# openhum3.net
KiCad netlist of a schematic drawn in EAGLE
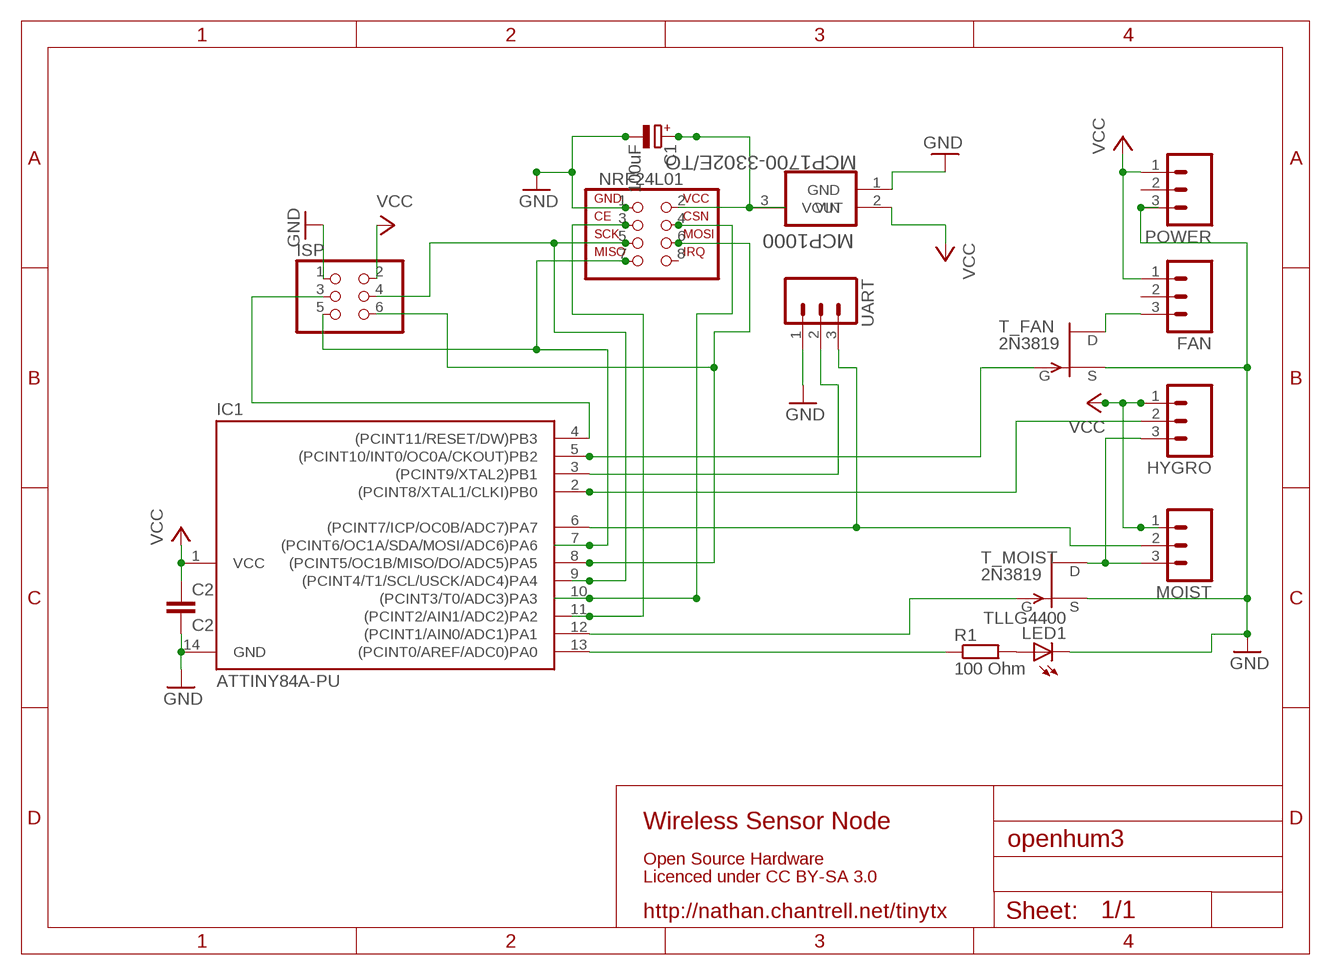
[diagram p0: schematic, sheet 1]

(export (version "E")
  (design (tool "Eeschema 10.0.6"))
  (components
    (comp (ref "C1")
      (value "100uF")
      (footprint "eagle-import:E2,5-6")
      (libsource (lib "eagle-import") (part "CPOL-EUE2.5-6"))
    )
    (comp (ref "C2")
      (value "C2")
      (footprint "eagle-import:C025-025X050")
      (libsource (lib "eagle-import") (part "C-EU025-025X050"))
    )
    (comp (ref "FAN")
      (value "M03JST-PTH")
      (footprint "eagle-import:JST-3-PTH")
      (libsource (lib "eagle-import") (part "M03JST-PTH"))
    )
    (comp (ref "HYGRO")
      (value "M03JST-PTH")
      (footprint "eagle-import:JST-3-PTH")
      (libsource (lib "eagle-import") (part "M03JST-PTH"))
    )
    (comp (ref "IC1")
      (value "ATTINY84A-PU")
      (footprint "eagle-import:DIL14")
      (libsource (lib "eagle-import") (part "TINY24/44/84-PU"))
    )
    (comp (ref "ISP")
      (value "PINHD-2X3")
      (footprint "eagle-import:2X03")
      (libsource (lib "eagle-import") (part "PINHD-2X3"))
    )
    (comp (ref "LED1")
      (value "TLLG4400")
      (footprint "eagle-import:LED3MM")
      (fields (field (name "MF") "VISHAY SEMICONDUCTOR"))
      (libsource (lib "eagle-import") (part "TLLG4400"))
    )
    (comp (ref "MCP1000")
      (value "MCP1700-3302E/TO")
      (footprint "eagle-import:TO127P254X495-3")
      (libsource (lib "eagle-import") (part "MCP1700-3302E/TO"))
    )
    (comp (ref "MOIST")
      (value "M03JST-PTH")
      (footprint "eagle-import:JST-3-PTH")
      (libsource (lib "eagle-import") (part "M03JST-PTH"))
    )
    (comp (ref "NRF24L01")
      (value "NRF24L01+")
      (footprint "eagle-import:NRF24L01+")
      (libsource (lib "eagle-import") (part "NRF24L01+"))
    )
    (comp (ref "POWER")
      (value "M03JST-PTH")
      (footprint "eagle-import:JST-3-PTH")
      (libsource (lib "eagle-import") (part "M03JST-PTH"))
    )
    (comp (ref "R1")
      (value "100 Ohm")
      (footprint "eagle-import:0204_5")
      (libsource (lib "eagle-import") (part "R-EU_0204/5"))
    )
    (comp (ref "T_FAN")
      (value "2N3819")
      (footprint "eagle-import:TO92")
      (libsource (lib "eagle-import") (part "2N3819"))
    )
    (comp (ref "T_MOIST")
      (value "2N3819")
      (footprint "eagle-import:TO92")
      (libsource (lib "eagle-import") (part "2N3819"))
    )
    (comp (ref "UART")
      (value "M03JST-PTH")
      (footprint "eagle-import:JST-3-PTH")
      (libsource (lib "eagle-import") (part "M03JST-PTH"))
    )
  )
  (nets
    (net (code "1") (name "GND") (class "Default")
      (node (ref "C1") (pin "-") (pinfunction "-_-") (pintype "passive"))
      (node (ref "C2") (pin "2") (pinfunction "2_2") (pintype "passive"))
      (node (ref "IC1") (pin "14") (pinfunction "GND_14") (pintype "power_in"))
      (node (ref "ISP") (pin "1") (pinfunction "1_1") (pintype "passive"))
      (node (ref "LED1") (pin "K") (pinfunction "C_K") (pintype "passive"))
      (node (ref "MCP1000") (pin "1") (pinfunction "GND_1") (pintype "passive"))
      (node (ref "NRF24L01") (pin "1") (pinfunction "1_1") (pintype "passive"))
      (node (ref "POWER") (pin "3") (pinfunction "3_3") (pintype "passive"))
      (node (ref "T_FAN") (pin "3") (pinfunction "S_3") (pintype "passive"))
      (node (ref "T_MOIST") (pin "3") (pinfunction "S_3") (pintype "passive"))
      (node (ref "UART") (pin "1") (pinfunction "1_1") (pintype "passive"))
    )
    (net (code "2") (name "Net-(IC1-(PCINT0{slash}AREF{slash}ADC0)PA0)") (class "Default")
      (node (ref "IC1") (pin "13") (pinfunction "(PCINT0/AREF/ADC0)PA0_13") (pintype "bidirectional"))
      (node (ref "R1") (pin "1") (pinfunction "1_1") (pintype "passive"))
    )
    (net (code "3") (name "Net-(IC1-(PCINT1{slash}AIN0{slash}ADC1)PA1)") (class "Default")
      (node (ref "IC1") (pin "12") (pinfunction "(PCINT1/AIN0/ADC1)PA1_12") (pintype "bidirectional"))
      (node (ref "T_MOIST") (pin "2") (pinfunction "G_2") (pintype "passive"))
    )
    (net (code "4") (name "Net-(IC1-(PCINT2{slash}AIN1{slash}ADC2)PA2)") (class "Default")
      (node (ref "IC1") (pin "11") (pinfunction "(PCINT2/AIN1/ADC2)PA2_11") (pintype "bidirectional"))
      (node (ref "NRF24L01") (pin "3") (pinfunction "3_3") (pintype "passive"))
    )
    (net (code "5") (name "Net-(IC1-(PCINT3{slash}T0{slash}ADC3)PA3)") (class "Default")
      (node (ref "IC1") (pin "10") (pinfunction "(PCINT3/T0/ADC3)PA3_10") (pintype "bidirectional"))
      (node (ref "NRF24L01") (pin "4") (pinfunction "4_4") (pintype "passive"))
    )
    (net (code "6") (name "Net-(IC1-(PCINT4{slash}T1{slash}SCL{slash}USCK{slash}ADC4)PA4)") (class "Default")
      (node (ref "IC1") (pin "9") (pinfunction "(PCINT4/T1/SCL/USCK/ADC4)PA4_9") (pintype "bidirectional"))
      (node (ref "ISP") (pin "4") (pinfunction "4_4") (pintype "passive"))
      (node (ref "NRF24L01") (pin "5") (pinfunction "5_5") (pintype "passive"))
    )
    (net (code "7") (name "Net-(IC1-(PCINT5{slash}OC1B{slash}MISO{slash}DO{slash}ADC5)PA5)") (class "Default")
      (node (ref "IC1") (pin "8") (pinfunction "(PCINT5/OC1B/MISO/DO/ADC5)PA5_8") (pintype "bidirectional"))
      (node (ref "ISP") (pin "6") (pinfunction "6_6") (pintype "passive"))
      (node (ref "NRF24L01") (pin "6") (pinfunction "6_6") (pintype "passive"))
    )
    (net (code "8") (name "Net-(IC1-(PCINT6{slash}OC1A{slash}SDA{slash}MOSI{slash}ADC6)PA6)") (class "Default")
      (node (ref "IC1") (pin "7") (pinfunction "(PCINT6/OC1A/SDA/MOSI/ADC6)PA6_7") (pintype "bidirectional"))
      (node (ref "ISP") (pin "5") (pinfunction "5_5") (pintype "passive"))
      (node (ref "NRF24L01") (pin "7") (pinfunction "7_7") (pintype "passive"))
    )
    (net (code "9") (name "Net-(IC1-(PCINT7{slash}ICP{slash}OC0B{slash}ADC7)PA7)") (class "Default")
      (node (ref "IC1") (pin "6") (pinfunction "(PCINT7/ICP/OC0B/ADC7)PA7_6") (pintype "bidirectional"))
      (node (ref "MOIST") (pin "2") (pinfunction "2_2") (pintype "passive"))
      (node (ref "UART") (pin "3") (pinfunction "3_3") (pintype "passive"))
    )
    (net (code "10") (name "Net-(IC1-(PCINT8{slash}XTAL1{slash}CLKI)PB0)") (class "Default")
      (node (ref "HYGRO") (pin "2") (pinfunction "2_2") (pintype "passive"))
      (node (ref "IC1") (pin "2") (pinfunction "(PCINT8/XTAL1/CLKI)PB0_2") (pintype "bidirectional"))
    )
    (net (code "11") (name "Net-(IC1-(PCINT9{slash}XTAL2)PB1)") (class "Default")
      (node (ref "IC1") (pin "3") (pinfunction "(PCINT9/XTAL2)PB1_3") (pintype "bidirectional"))
      (node (ref "UART") (pin "2") (pinfunction "2_2") (pintype "passive"))
    )
    (net (code "12") (name "Net-(IC1-(PCINT10{slash}INT0{slash}OC0A{slash}CKOUT)PB2)") (class "Default")
      (node (ref "IC1") (pin "5") (pinfunction "(PCINT10/INT0/OC0A/CKOUT)PB2_5") (pintype "bidirectional"))
      (node (ref "T_FAN") (pin "2") (pinfunction "G_2") (pintype "passive"))
    )
    (net (code "13") (name "Net-(IC1-(PCINT11{slash}RESET{slash}DW)PB3)") (class "Default")
      (node (ref "IC1") (pin "4") (pinfunction "(PCINT11/RESET/DW)PB3_4") (pintype "bidirectional"))
      (node (ref "ISP") (pin "3") (pinfunction "3_3") (pintype "passive"))
    )
    (net (code "14") (name "Net-(LED1-PadA)") (class "Default")
      (node (ref "LED1") (pin "A") (pinfunction "A_A") (pintype "passive"))
      (node (ref "R1") (pin "2") (pinfunction "2_2") (pintype "passive"))
    )
    (net (code "15") (name "Net-(MCP1000-VOUT)") (class "Default")
      (node (ref "C1") (pin "+") (pinfunction "+_+") (pintype "passive"))
      (node (ref "MCP1000") (pin "3") (pinfunction "VOUT_3") (pintype "output"))
      (node (ref "NRF24L01") (pin "2") (pinfunction "2_2") (pintype "passive"))
    )
    (net (code "16") (name "Net-(T_FAN-D)") (class "Default")
      (node (ref "FAN") (pin "3") (pinfunction "3_3") (pintype "passive"))
      (node (ref "T_FAN") (pin "1") (pinfunction "D_1") (pintype "passive"))
    )
    (net (code "17") (name "Net-(T_MOIST-D)") (class "Default")
      (node (ref "HYGRO") (pin "3") (pinfunction "3_3") (pintype "passive"))
      (node (ref "MOIST") (pin "3") (pinfunction "3_3") (pintype "passive"))
      (node (ref "T_MOIST") (pin "1") (pinfunction "D_1") (pintype "passive"))
    )
    (net (code "18") (name "VCC") (class "Default")
      (node (ref "C2") (pin "1") (pinfunction "1_1") (pintype "passive"))
      (node (ref "FAN") (pin "1") (pinfunction "1_1") (pintype "passive"))
      (node (ref "HYGRO") (pin "1") (pinfunction "1_1") (pintype "passive"))
      (node (ref "IC1") (pin "1") (pinfunction "VCC_1") (pintype "power_in"))
      (node (ref "ISP") (pin "2") (pinfunction "2_2") (pintype "passive"))
      (node (ref "MCP1000") (pin "2") (pinfunction "VIN_2") (pintype "input"))
      (node (ref "MOIST") (pin "1") (pinfunction "1_1") (pintype "passive"))
      (node (ref "POWER") (pin "1") (pinfunction "1_1") (pintype "passive"))
    )
    (net (code "19") (name "unconnected-(FAN-Pad2)") (class "Default")
      (node (ref "FAN") (pin "2") (pinfunction "2_2") (pintype "passive"))
    )
    (net (code "20") (name "unconnected-(NRF24L01-Pad8)") (class "Default")
      (node (ref "NRF24L01") (pin "8") (pinfunction "8_8") (pintype "passive"))
    )
    (net (code "21") (name "unconnected-(POWER-Pad2)") (class "Default")
      (node (ref "POWER") (pin "2") (pinfunction "2_2") (pintype "passive"))
    )
  )
)
